# LitVP-02.net
KiCad netlist of a schematic drawn in Altium Designer
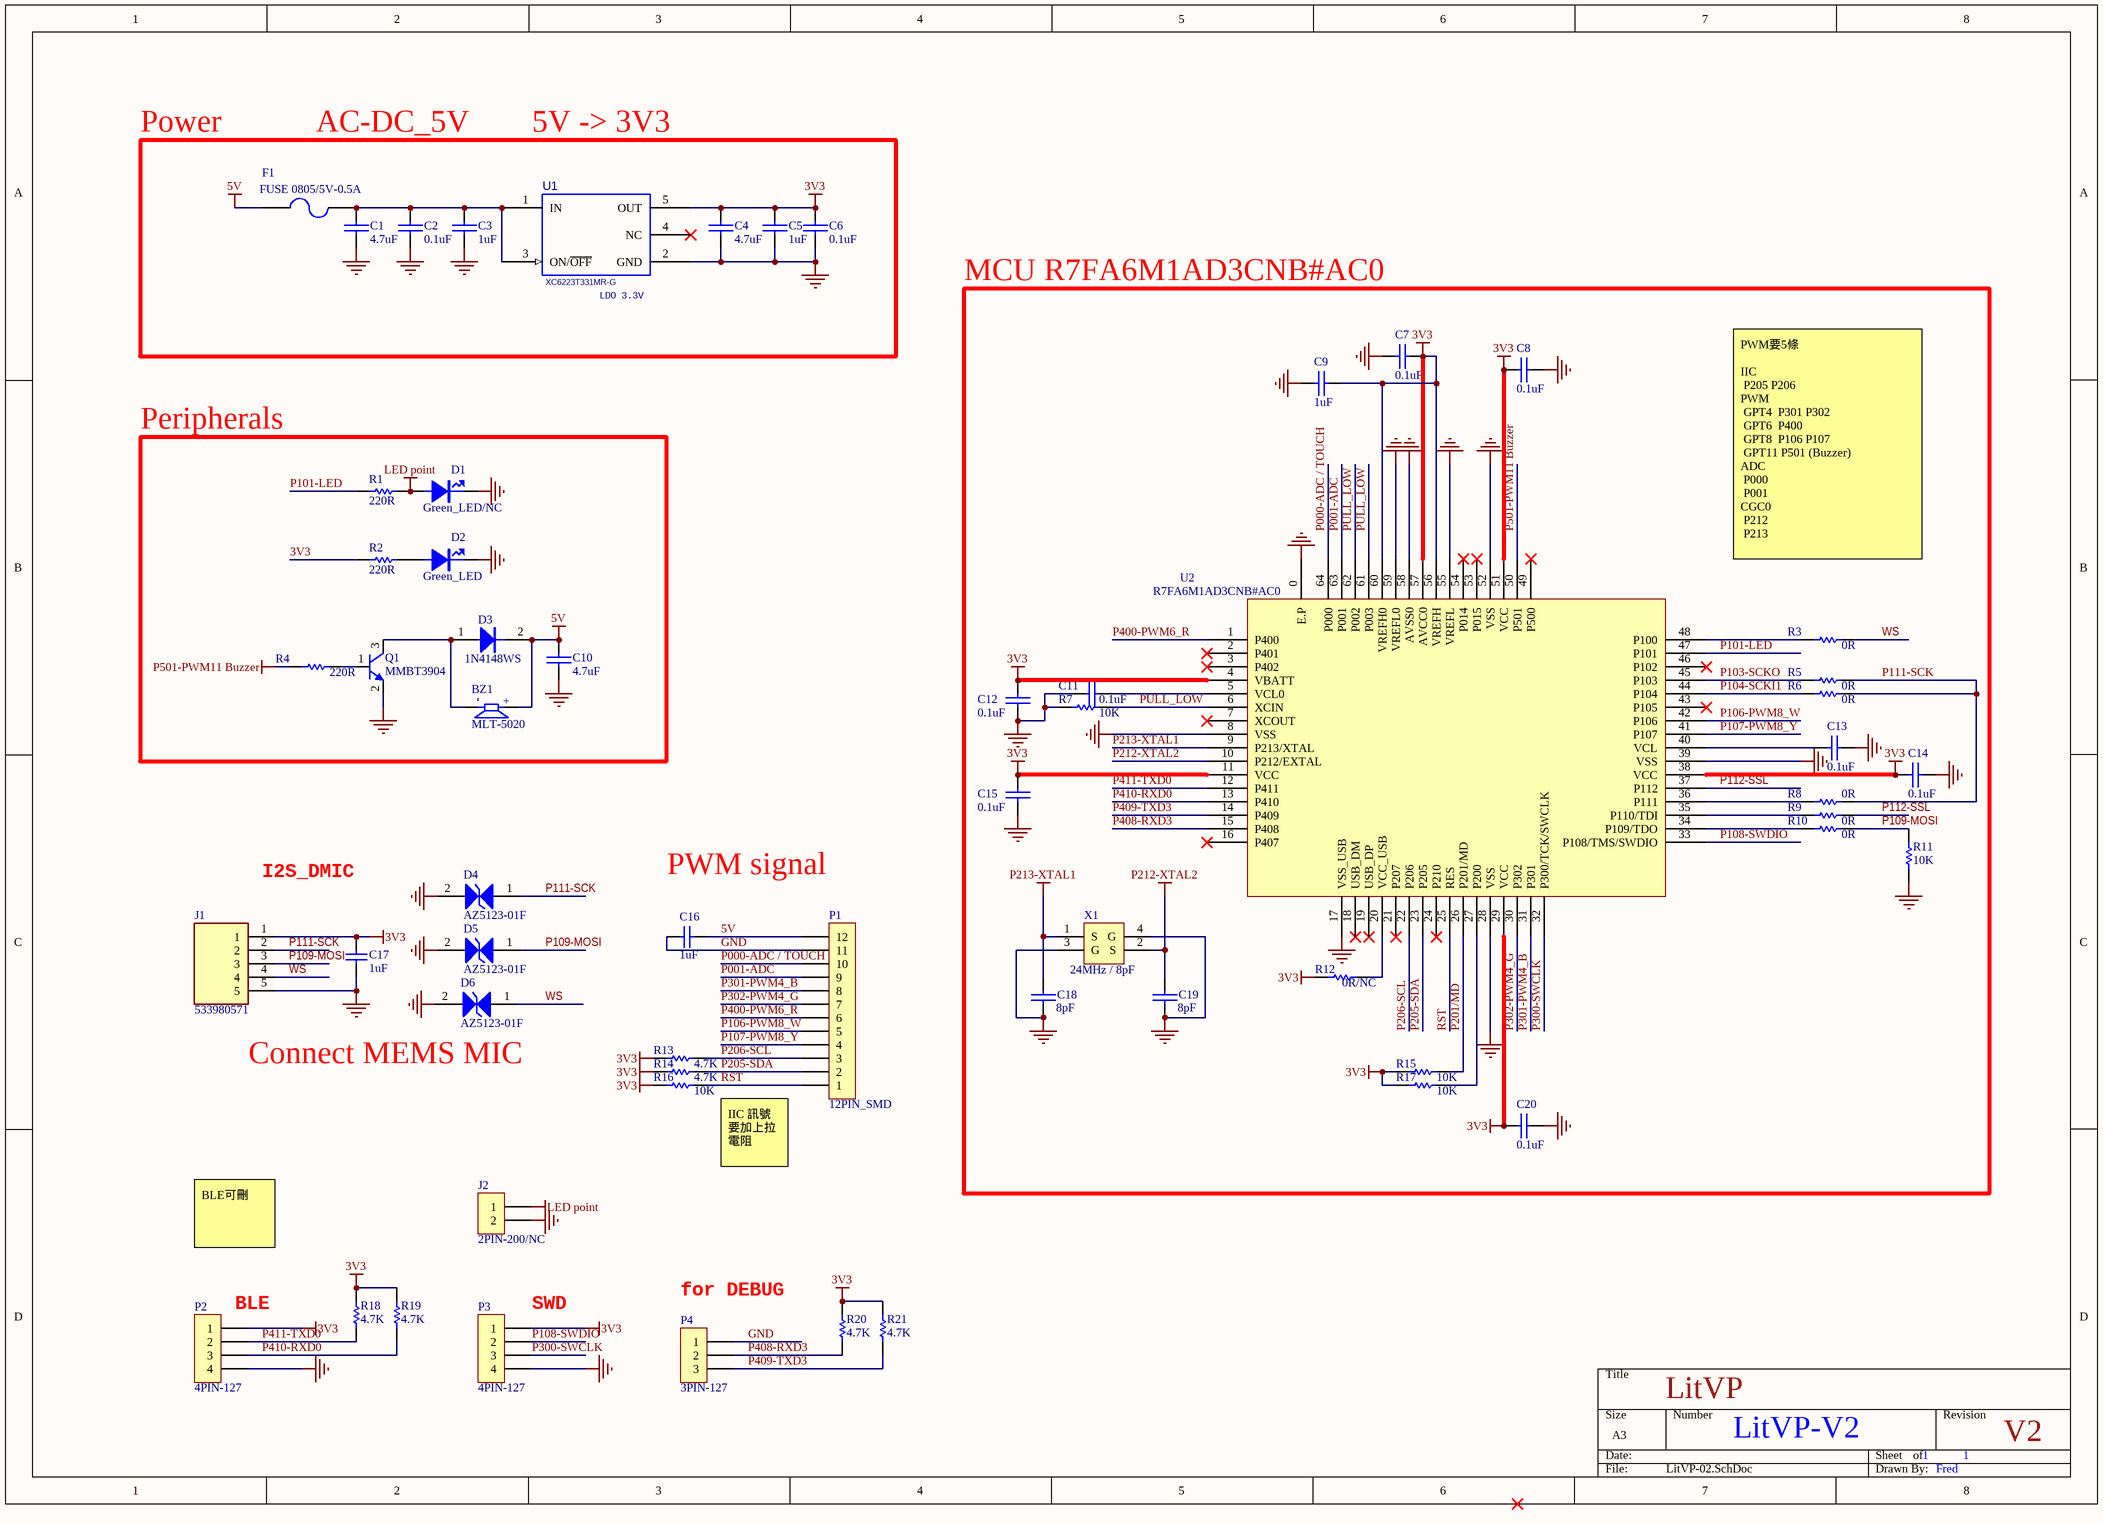
[diagram p0: LitVP-02.SchDoc]

(export (version "E")
  (design (tool "Eeschema 10.0.6"))
  (components
    (comp (ref "BZ1")
      (value "MLT-5020")
      (footprint "BUZZER-SMD-5*5mm")
      (description "Buzzer")
      (libsource (lib "*") (part "YZ5020CS-03L-4.0-12-R"))
    )
    (comp (ref "C1")
      (value "4.7uF")
      (footprint "0402C")
      (description "Capacitor")
      (libsource (lib "CAP") (part "CAP"))
    )
    (comp (ref "C2")
      (value "0.1uF")
      (footprint "0402C")
      (description "Capacitor")
      (libsource (lib "CAP") (part "CAP"))
    )
    (comp (ref "C3")
      (value "1uF")
      (footprint "0402C")
      (description "Capacitor")
      (libsource (lib "CAP") (part "CAP"))
    )
    (comp (ref "C4")
      (value "4.7uF")
      (footprint "0402C")
      (description "Capacitor")
      (libsource (lib "CAP") (part "CAP"))
    )
    (comp (ref "C5")
      (value "1uF")
      (footprint "0402C")
      (description "Capacitor")
      (libsource (lib "CAP") (part "CAP"))
    )
    (comp (ref "C6")
      (value "0.1uF")
      (footprint "0402C")
      (description "Capacitor")
      (libsource (lib "CAP") (part "CAP"))
    )
    (comp (ref "C7")
      (value "0.1uF")
      (footprint "0402C")
      (description "Capacitor")
      (libsource (lib "CAP") (part "CAP"))
    )
    (comp (ref "C8")
      (value "0.1uF")
      (footprint "0402C")
      (description "Capacitor")
      (libsource (lib "CAP") (part "CAP"))
    )
    (comp (ref "C9")
      (value "1uF")
      (footprint "0402C")
      (description "Capacitor")
      (libsource (lib "CAP") (part "CAP"))
    )
    (comp (ref "C10")
      (value "4.7uF")
      (footprint "0402C")
      (description "Capacitor")
      (libsource (lib "CAP") (part "CAP"))
    )
    (comp (ref "C11")
      (value "0.1uF")
      (footprint "0402C")
      (description "Capacitor")
      (libsource (lib "CAP") (part "CAP"))
    )
    (comp (ref "C12")
      (value "0.1uF")
      (footprint "0402C")
      (description "Capacitor")
      (libsource (lib "CAP") (part "CAP"))
    )
    (comp (ref "C13")
      (value "0.1uF")
      (footprint "0402C")
      (description "Capacitor")
      (libsource (lib "CAP") (part "CAP"))
    )
    (comp (ref "C14")
      (value "0.1uF")
      (footprint "0402C")
      (description "Capacitor")
      (libsource (lib "CAP") (part "CAP"))
    )
    (comp (ref "C15")
      (value "0.1uF")
      (footprint "0402C")
      (description "Capacitor")
      (libsource (lib "CAP") (part "CAP"))
    )
    (comp (ref "C16")
      (value "1uF")
      (footprint "0402C")
      (description "Capacitor")
      (libsource (lib "*") (part "Cap Semi"))
    )
    (comp (ref "C17")
      (value "1uF")
      (footprint "0402C")
      (description "Capacitor")
      (libsource (lib "*") (part "Cap Semi"))
    )
    (comp (ref "C18")
      (value "8pF")
      (footprint "0402C")
      (description "Capacitor")
      (libsource (lib "*") (part "CAP"))
    )
    (comp (ref "C19")
      (value "8pF")
      (footprint "0402C")
      (description "Capacitor")
      (libsource (lib "*") (part "CAP"))
    )
    (comp (ref "C20")
      (value "0.1uF")
      (footprint "0402C")
      (description "Capacitor")
      (libsource (lib "CAP") (part "CAP"))
    )
    (comp (ref "D1")
      (value "Green_LED/NC")
      (footprint "LED0603--0.4mm")
      (fields
        (field (name "MANUFACTURER'S PART NUMBER") "CL-170G-CD-T")
        (field (name "PART NUMBER") "41100017000")
        (field (name "MANUFACTURER") "Citizen")
      )
      (libsource (lib "*") (part "LED"))
    )
    (comp (ref "D2")
      (value "Green_LED")
      (footprint "LED0603--0.4mm")
      (fields
        (field (name "MANUFACTURER'S PART NUMBER") "CL-170G-CD-T")
        (field (name "PART NUMBER") "41100017000")
        (field (name "MANUFACTURER") "Citizen")
      )
      (libsource (lib "*") (part "LED"))
    )
    (comp (ref "D3") (value "1N4148WS") (footprint "SOD323-1N4148WS") (libsource (lib "*") (part "DIODE")))
    (comp (ref "D4")
      (value "AZ5123-01F")
      (footprint "DIODE-0402")
      (description "ESD")
      (libsource (lib "*") (part "PESD5V0L1BA"))
    )
    (comp (ref "D5")
      (value "AZ5123-01F")
      (footprint "DIODE-0402")
      (description "ESD")
      (libsource (lib "*") (part "PESD5V0L1BA"))
    )
    (comp (ref "D6")
      (value "AZ5123-01F")
      (footprint "DIODE-0402")
      (description "ESD")
      (libsource (lib "*") (part "PESD5V0L1BA"))
    )
    (comp (ref "F1")
      (value "FUSE 0805/5V-0.5A")
      (footprint "0805")
      (description "Fuse")
      (libsource (lib "*") (part "FUSE2"))
    )
    (comp (ref "J1")
      (value "533980571")
      (footprint "SamacSys:53398-0571")
      (description "Connector")
      (fields (field (name "MANUFACTURER_PART_NUMBER") "53048-0510"))
      (libsource (lib "*") (part "53048-0510"))
    )
    (comp (ref "J2")
      (value "2PIN-200/NC")
      (footprint "2PIN-127")
      (description "Connector")
      (libsource (lib "PIN") (part "2PIN-200"))
    )
    (comp (ref "P1")
      (value "12PIN_SMD")
      (footprint "12PIN_SAMTEC-MMT-136-02-X-SH")
      (libsource (lib "PIN") (part "12PIN_SMD"))
    )
    (comp (ref "P2")
      (value "4PIN-127")
      (footprint "4PIN-127")
      (description "1.27mm Header")
      (libsource (lib "*") (part "CON4"))
    )
    (comp (ref "P3")
      (value "4PIN-127")
      (footprint "4PIN-127")
      (description "1.27mm Header")
      (libsource (lib "*") (part "CON4"))
    )
    (comp (ref "P4") (value "3PIN-127") (footprint "3PIN-127") (libsource (lib "PIN") (part "3PIN-127")))
    (comp (ref "Q1")
      (value "MMBT3904")
      (footprint "SOT-23")
      (description "NPN General Purpose Amplifier")
      (fields (field (name "PUBLISHER") "*"))
      (libsource (lib "*") (part "NPN-3"))
    )
    (comp (ref "R1")
      (value "220R")
      (footprint "0402")
      (description "Resistor")
      (libsource (lib "*") (part "Res Semi"))
    )
    (comp (ref "R2")
      (value "220R")
      (footprint "0402")
      (description "Resistor")
      (libsource (lib "*") (part "Res Semi"))
    )
    (comp (ref "R3")
      (value "0R")
      (footprint "0402")
      (description "Resistor")
      (libsource (lib "*") (part "Res Semi"))
    )
    (comp (ref "R4")
      (value "220R")
      (footprint "0402")
      (description "Resistor")
      (libsource (lib "*") (part "Res Semi"))
    )
    (comp (ref "R5")
      (value "0R")
      (footprint "0402")
      (description "Resistor")
      (libsource (lib "*") (part "Res Semi"))
    )
    (comp (ref "R6")
      (value "0R")
      (footprint "0402")
      (description "Resistor")
      (libsource (lib "*") (part "Res Semi"))
    )
    (comp (ref "R7")
      (value "10K")
      (footprint "0402")
      (description "Resistor")
      (libsource (lib "*") (part "Res Semi"))
    )
    (comp (ref "R8")
      (value "0R")
      (footprint "0402")
      (description "Resistor")
      (libsource (lib "*") (part "Res Semi"))
    )
    (comp (ref "R9")
      (value "0R")
      (footprint "0402")
      (description "Resistor")
      (libsource (lib "*") (part "Res Semi"))
    )
    (comp (ref "R10")
      (value "0R")
      (footprint "0402")
      (description "Resistor")
      (libsource (lib "*") (part "Res Semi"))
    )
    (comp (ref "R11")
      (value "10K")
      (footprint "0402")
      (description "Resistor")
      (libsource (lib "*") (part "Res Semi"))
    )
    (comp (ref "R12")
      (value "0R/NC")
      (footprint "0402")
      (description "Resistor")
      (libsource (lib "*") (part "Res Semi"))
    )
    (comp (ref "R13")
      (value "4.7K")
      (footprint "0402")
      (description "Resistor")
      (libsource (lib "*") (part "Res Semi"))
    )
    (comp (ref "R14")
      (value "4.7K")
      (footprint "0402")
      (description "Resistor")
      (libsource (lib "*") (part "Res Semi"))
    )
    (comp (ref "R15")
      (value "10K")
      (footprint "0402")
      (description "Resistor")
      (libsource (lib "*") (part "Res Semi"))
    )
    (comp (ref "R16")
      (value "10K")
      (footprint "0402")
      (description "Resistor")
      (libsource (lib "*") (part "Res Semi"))
    )
    (comp (ref "R17")
      (value "10K")
      (footprint "0402")
      (description "Resistor")
      (libsource (lib "*") (part "Res Semi"))
    )
    (comp (ref "R18")
      (value "4.7K")
      (footprint "0402")
      (description "Resistor")
      (libsource (lib "*") (part "Res Semi"))
    )
    (comp (ref "R19")
      (value "4.7K")
      (footprint "0402")
      (description "Resistor")
      (libsource (lib "*") (part "Res Semi"))
    )
    (comp (ref "R20")
      (value "4.7K")
      (footprint "0402")
      (description "Resistor")
      (libsource (lib "*") (part "Res Semi"))
    )
    (comp (ref "R21")
      (value "4.7K")
      (footprint "0402")
      (description "Resistor")
      (libsource (lib "*") (part "Res Semi"))
    )
    (comp (ref "U1")
      (value "XC6223T331MR-G")
      (footprint "SOT-23-5-0.95MM")
      (libsource (lib "*") (part "XC6223T331MR-G"))
    )
    (comp (ref "U2")
      (value "R7FA6M1AD3CNB#AC0")
      (footprint "QFN64-0.4mm-8X8")
      (description "MCU")
      (libsource (lib "*") (part "R7FA6M1AD3CNB#AC0"))
    )
    (comp (ref "X1")
      (value "24MHz / 8pF")
      (footprint "XTAL-SMD-20X16")
      (libsource (lib "*") (part "XTAL-SMD-25*32"))
    )
  )
  (nets
    (net (code "1") (name "/P000-ADC {slash} TOUCH") (class "Default")
      (node (ref "P1") (pin "10") (pinfunction "10_10") (pintype "passive"))
      (node (ref "U2") (pin "64") (pinfunction "P000_64") (pintype "passive"))
    )
    (net (code "2") (name "/P001-ADC") (class "Default")
      (node (ref "P1") (pin "9") (pinfunction "9_9") (pintype "passive"))
      (node (ref "U2") (pin "63") (pinfunction "P001_63") (pintype "passive"))
    )
    (net (code "3") (name "/P101-LED") (class "Default")
      (node (ref "R1") (pin "1") (pinfunction "1_1") (pintype "passive"))
      (node (ref "U2") (pin "47") (pinfunction "P101_47") (pintype "passive"))
    )
    (net (code "4") (name "/P103-SCKO") (class "Default")
      (node (ref "R5") (pin "2") (pinfunction "2_2") (pintype "passive"))
      (node (ref "U2") (pin "45") (pinfunction "P103_45") (pintype "passive"))
    )
    (net (code "5") (name "/P104-SCKI1") (class "Default")
      (node (ref "R6") (pin "2") (pinfunction "2_2") (pintype "passive"))
      (node (ref "U2") (pin "44") (pinfunction "P104_44") (pintype "passive"))
    )
    (net (code "6") (name "/P106-PWM8_W") (class "Default")
      (node (ref "P1") (pin "5") (pinfunction "5_5") (pintype "passive"))
      (node (ref "U2") (pin "42") (pinfunction "P106_42") (pintype "passive"))
    )
    (net (code "7") (name "/P107-PWM8_Y") (class "Default")
      (node (ref "P1") (pin "4") (pinfunction "4_4") (pintype "passive"))
      (node (ref "U2") (pin "41") (pinfunction "P107_41") (pintype "passive"))
    )
    (net (code "8") (name "/P108-SWDIO") (class "Default")
      (node (ref "P3") (pin "2") (pinfunction "2_2") (pintype "passive"))
      (node (ref "U2") (pin "33") (pinfunction "P108/TMS/SWDIO_33") (pintype "passive"))
    )
    (net (code "9") (name "/P109-MOSI") (class "Default")
      (node (ref "D5") (pin "1") (pinfunction "1_1") (pintype "passive"))
      (node (ref "J1") (pin "3") (pinfunction "3_3") (pintype "passive"))
      (node (ref "R10") (pin "1") (pinfunction "1_1") (pintype "passive"))
      (node (ref "R11") (pin "2") (pinfunction "2_2") (pintype "passive"))
    )
    (net (code "10") (name "/P111-SCK") (class "Default")
      (node (ref "D4") (pin "1") (pinfunction "1_1") (pintype "passive"))
      (node (ref "J1") (pin "2") (pinfunction "2_2") (pintype "passive"))
      (node (ref "R5") (pin "1") (pinfunction "1_1") (pintype "passive"))
      (node (ref "R6") (pin "1") (pinfunction "1_1") (pintype "passive"))
      (node (ref "R8") (pin "1") (pinfunction "1_1") (pintype "passive"))
    )
    (net (code "11") (name "/P112-SSL") (class "Default")
      (node (ref "R9") (pin "1") (pinfunction "1_1") (pintype "passive"))
      (node (ref "U2") (pin "37") (pinfunction "P112_37") (pintype "passive"))
    )
    (net (code "12") (name "/P201{slash}MD") (class "Default")
      (node (ref "R15") (pin "1") (pinfunction "1_1") (pintype "passive"))
      (node (ref "U2") (pin "26") (pinfunction "P201/MD_26") (pintype "passive"))
    )
    (net (code "13") (name "/P205-SDA") (class "Default")
      (node (ref "P1") (pin "2") (pinfunction "2_2") (pintype "passive"))
      (node (ref "R14") (pin "1") (pinfunction "1_1") (pintype "passive"))
      (node (ref "U2") (pin "23") (pinfunction "P205_23") (pintype "passive"))
    )
    (net (code "14") (name "/P206-SCL") (class "Default")
      (node (ref "P1") (pin "3") (pinfunction "3_3") (pintype "passive"))
      (node (ref "R13") (pin "1") (pinfunction "1_1") (pintype "passive"))
      (node (ref "U2") (pin "22") (pinfunction "P206_22") (pintype "passive"))
    )
    (net (code "15") (name "/P300-SWCLK") (class "Default")
      (node (ref "P3") (pin "3") (pinfunction "3_3") (pintype "passive"))
      (node (ref "U2") (pin "32") (pinfunction "P300/TCK/SWCLK_32") (pintype "passive"))
    )
    (net (code "16") (name "/P301-PWM4_B") (class "Default")
      (node (ref "P1") (pin "8") (pinfunction "8_8") (pintype "passive"))
      (node (ref "U2") (pin "31") (pinfunction "P301_31") (pintype "passive"))
    )
    (net (code "17") (name "/P302-PWM4_G") (class "Default")
      (node (ref "P1") (pin "7") (pinfunction "7_7") (pintype "passive"))
      (node (ref "U2") (pin "30") (pinfunction "P302_30") (pintype "passive"))
    )
    (net (code "18") (name "/P400-PWM6_R") (class "Default")
      (node (ref "P1") (pin "6") (pinfunction "6_6") (pintype "passive"))
      (node (ref "U2") (pin "1") (pinfunction "P400_1") (pintype "passive"))
    )
    (net (code "19") (name "/P408-RXD3") (class "Default")
      (node (ref "P4") (pin "2") (pinfunction "2_2") (pintype "passive"))
      (node (ref "R20") (pin "2") (pinfunction "2_2") (pintype "passive"))
      (node (ref "U2") (pin "15") (pinfunction "P408_15") (pintype "passive"))
    )
    (net (code "20") (name "/P409-TXD3") (class "Default")
      (node (ref "P4") (pin "3") (pinfunction "3_3") (pintype "passive"))
      (node (ref "R21") (pin "2") (pinfunction "2_2") (pintype "passive"))
      (node (ref "U2") (pin "14") (pinfunction "P409_14") (pintype "passive"))
    )
    (net (code "21") (name "/P410-RXD0") (class "Default")
      (node (ref "P2") (pin "3") (pinfunction "3_3") (pintype "passive"))
      (node (ref "R19") (pin "2") (pinfunction "2_2") (pintype "passive"))
      (node (ref "U2") (pin "13") (pinfunction "P410_13") (pintype "passive"))
    )
    (net (code "22") (name "/P411-TXD0") (class "Default")
      (node (ref "P2") (pin "2") (pinfunction "2_2") (pintype "passive"))
      (node (ref "R18") (pin "2") (pinfunction "2_2") (pintype "passive"))
      (node (ref "U2") (pin "12") (pinfunction "P411_12") (pintype "passive"))
    )
    (net (code "23") (name "/PULL_LOW") (class "Default")
      (node (ref "R7") (pin "1") (pinfunction "1_1") (pintype "passive"))
      (node (ref "U2") (pin "6") (pinfunction "XCIN_6") (pintype "passive"))
      (node (ref "U2") (pin "61") (pinfunction "P003_61") (pintype "passive"))
      (node (ref "U2") (pin "62") (pinfunction "P002_62") (pintype "passive"))
    )
    (net (code "24") (name "/RST") (class "Default")
      (node (ref "P1") (pin "1") (pinfunction "1_1") (pintype "passive"))
      (node (ref "R16") (pin "1") (pinfunction "1_1") (pintype "passive"))
      (node (ref "U2") (pin "25") (pinfunction "RES_25") (pintype "passive"))
    )
    (net (code "25") (name "/WS") (class "Default")
      (node (ref "D6") (pin "1") (pinfunction "1_1") (pintype "passive"))
      (node (ref "J1") (pin "4") (pinfunction "4_4") (pintype "passive"))
      (node (ref "R3") (pin "1") (pinfunction "1_1") (pintype "passive"))
    )
    (net (code "26") (name "3V3") (class "Default")
      (node (ref "C12") (pin "2") (pinfunction "2_2") (pintype "passive"))
      (node (ref "C14") (pin "2") (pinfunction "2_2") (pintype "passive"))
      (node (ref "C15") (pin "2") (pinfunction "2_2") (pintype "passive"))
      (node (ref "C17") (pin "2") (pinfunction "2_2") (pintype "passive"))
      (node (ref "C20") (pin "2") (pinfunction "2_2") (pintype "passive"))
      (node (ref "C4") (pin "1") (pinfunction "1_1") (pintype "passive"))
      (node (ref "C5") (pin "1") (pinfunction "1_1") (pintype "passive"))
      (node (ref "C6") (pin "1") (pinfunction "1_1") (pintype "passive"))
      (node (ref "C7") (pin "2") (pinfunction "2_2") (pintype "passive"))
      (node (ref "C8") (pin "1") (pinfunction "1_1") (pintype "passive"))
      (node (ref "C9") (pin "2") (pinfunction "2_2") (pintype "passive"))
      (node (ref "J1") (pin "1") (pinfunction "1_1") (pintype "passive"))
      (node (ref "P2") (pin "1") (pinfunction "1_1") (pintype "passive"))
      (node (ref "P3") (pin "1") (pinfunction "1_1") (pintype "passive"))
      (node (ref "R12") (pin "2") (pinfunction "2_2") (pintype "passive"))
      (node (ref "R13") (pin "2") (pinfunction "2_2") (pintype "passive"))
      (node (ref "R14") (pin "2") (pinfunction "2_2") (pintype "passive"))
      (node (ref "R15") (pin "2") (pinfunction "2_2") (pintype "passive"))
      (node (ref "R16") (pin "2") (pinfunction "2_2") (pintype "passive"))
      (node (ref "R17") (pin "2") (pinfunction "2_2") (pintype "passive"))
      (node (ref "R18") (pin "1") (pinfunction "1_1") (pintype "passive"))
      (node (ref "R19") (pin "1") (pinfunction "1_1") (pintype "passive"))
      (node (ref "R2") (pin "1") (pinfunction "1_1") (pintype "passive"))
      (node (ref "R20") (pin "1") (pinfunction "1_1") (pintype "passive"))
      (node (ref "R21") (pin "1") (pinfunction "1_1") (pintype "passive"))
      (node (ref "U1") (pin "5") (pinfunction "OUT_5") (pintype "passive"))
      (node (ref "U2") (pin "11") (pinfunction "VCC_11") (pintype "passive"))
      (node (ref "U2") (pin "29") (pinfunction "VCC_29") (pintype "passive"))
      (node (ref "U2") (pin "38") (pinfunction "VCC_38") (pintype "passive"))
      (node (ref "U2") (pin "4") (pinfunction "VBATT_4") (pintype "passive"))
      (node (ref "U2") (pin "51") (pinfunction "VCC_51") (pintype "passive"))
      (node (ref "U2") (pin "56") (pinfunction "VREFH_56") (pintype "passive"))
      (node (ref "U2") (pin "57") (pinfunction "AVCC0_57") (pintype "passive"))
      (node (ref "U2") (pin "60") (pinfunction "VREFH0_60") (pintype "passive"))
    )
    (net (code "27") (name "5V") (class "Default")
      (node (ref "BZ1") (pin "1") (pinfunction "1_1") (pintype "passive"))
      (node (ref "C10") (pin "1") (pinfunction "1_1") (pintype "passive"))
      (node (ref "C16") (pin "1") (pinfunction "1_1") (pintype "passive"))
      (node (ref "D3") (pin "2") (pinfunction "2_2") (pintype "passive"))
      (node (ref "F1") (pin "1") (pinfunction "1_1") (pintype "passive"))
      (node (ref "P1") (pin "12") (pinfunction "12_12") (pintype "passive"))
    )
    (net (code "28") (name "GND") (class "Default")
      (node (ref "C1") (pin "2") (pinfunction "2_2") (pintype "passive"))
      (node (ref "C10") (pin "2") (pinfunction "2_2") (pintype "passive"))
      (node (ref "C11") (pin "2") (pinfunction "2_2") (pintype "passive"))
      (node (ref "C12") (pin "1") (pinfunction "1_1") (pintype "passive"))
      (node (ref "C13") (pin "1") (pinfunction "1_1") (pintype "passive"))
      (node (ref "C14") (pin "1") (pinfunction "1_1") (pintype "passive"))
      (node (ref "C15") (pin "1") (pinfunction "1_1") (pintype "passive"))
      (node (ref "C16") (pin "2") (pinfunction "2_2") (pintype "passive"))
      (node (ref "C17") (pin "1") (pinfunction "1_1") (pintype "passive"))
      (node (ref "C18") (pin "2") (pinfunction "2_2") (pintype "passive"))
      (node (ref "C19") (pin "2") (pinfunction "2_2") (pintype "passive"))
      (node (ref "C2") (pin "2") (pinfunction "2_2") (pintype "passive"))
      (node (ref "C20") (pin "1") (pinfunction "1_1") (pintype "passive"))
      (node (ref "C3") (pin "2") (pinfunction "2_2") (pintype "passive"))
      (node (ref "C4") (pin "2") (pinfunction "2_2") (pintype "passive"))
      (node (ref "C5") (pin "2") (pinfunction "2_2") (pintype "passive"))
      (node (ref "C6") (pin "2") (pinfunction "2_2") (pintype "passive"))
      (node (ref "C7") (pin "1") (pinfunction "1_1") (pintype "passive"))
      (node (ref "C8") (pin "2") (pinfunction "2_2") (pintype "passive"))
      (node (ref "C9") (pin "1") (pinfunction "1_1") (pintype "passive"))
      (node (ref "D1") (pin "2") (pinfunction "2_2") (pintype "passive"))
      (node (ref "D2") (pin "2") (pinfunction "2_2") (pintype "passive"))
      (node (ref "D4") (pin "2") (pinfunction "2_2") (pintype "passive"))
      (node (ref "D5") (pin "2") (pinfunction "2_2") (pintype "passive"))
      (node (ref "D6") (pin "2") (pinfunction "2_2") (pintype "passive"))
      (node (ref "J1") (pin "5") (pinfunction "5_5") (pintype "passive"))
      (node (ref "J2") (pin "2") (pinfunction "2_2") (pintype "passive"))
      (node (ref "P1") (pin "11") (pinfunction "11_11") (pintype "passive"))
      (node (ref "P2") (pin "4") (pinfunction "4_4") (pintype "passive"))
      (node (ref "P3") (pin "4") (pinfunction "4_4") (pintype "passive"))
      (node (ref "P4") (pin "1") (pinfunction "1_1") (pintype "passive"))
      (node (ref "Q1") (pin "2") (pinfunction "E_2") (pintype "passive"))
      (node (ref "R11") (pin "1") (pinfunction "1_1") (pintype "passive"))
      (node (ref "R7") (pin "2") (pinfunction "2_2") (pintype "passive"))
      (node (ref "U1") (pin "2") (pinfunction "GND_2") (pintype "passive"))
      (node (ref "U2") (pin "0") (pinfunction "E.P_0") (pintype "passive"))
      (node (ref "U2") (pin "17") (pinfunction "VSS_USB_17") (pintype "passive"))
      (node (ref "U2") (pin "28") (pinfunction "VSS_28") (pintype "passive"))
      (node (ref "U2") (pin "39") (pinfunction "VSS_39") (pintype "passive"))
      (node (ref "U2") (pin "52") (pinfunction "VSS_52") (pintype "passive"))
      (node (ref "U2") (pin "55") (pinfunction "VREFL_55") (pintype "passive"))
      (node (ref "U2") (pin "58") (pinfunction "AVSS0_58") (pintype "passive"))
      (node (ref "U2") (pin "59") (pinfunction "VREFL0_59") (pintype "passive"))
      (node (ref "U2") (pin "8") (pinfunction "VSS_8") (pintype "passive"))
      (node (ref "X1") (pin "3") (pinfunction "G_3") (pintype "passive"))
      (node (ref "X1") (pin "4") (pinfunction "G_4") (pintype "passive"))
    )
    (net (code "29") (name "LED point") (class "Default")
      (node (ref "D1") (pin "1") (pinfunction "1_1") (pintype "passive"))
      (node (ref "J2") (pin "1") (pinfunction "1_1") (pintype "passive"))
      (node (ref "R1") (pin "2") (pinfunction "2_2") (pintype "passive"))
    )
    (net (code "30") (name "Net-(D2-Pad1)") (class "Default")
      (node (ref "D2") (pin "1") (pinfunction "1_1") (pintype "passive"))
      (node (ref "R2") (pin "2") (pinfunction "2_2") (pintype "passive"))
    )
    (net (code "31") (name "Net-(Q1-B)") (class "Default")
      (node (ref "Q1") (pin "1") (pinfunction "B_1") (pintype "passive"))
      (node (ref "R4") (pin "1") (pinfunction "1_1") (pintype "passive"))
    )
    (net (code "32") (name "Net-(Q1-C)") (class "Default")
      (node (ref "BZ1") (pin "2") (pinfunction "2_2") (pintype "passive"))
      (node (ref "D3") (pin "1") (pinfunction "1_1") (pintype "passive"))
      (node (ref "Q1") (pin "3") (pinfunction "C_3") (pintype "passive"))
    )
    (net (code "33") (name "Net-(U1-IN)") (class "Default")
      (node (ref "C1") (pin "1") (pinfunction "1_1") (pintype "passive"))
      (node (ref "C2") (pin "1") (pinfunction "1_1") (pintype "passive"))
      (node (ref "C3") (pin "1") (pinfunction "1_1") (pintype "passive"))
      (node (ref "F1") (pin "2") (pinfunction "2_2") (pintype "passive"))
      (node (ref "U1") (pin "1") (pinfunction "IN_1") (pintype "passive"))
      (node (ref "U1") (pin "3") (pinfunction "ON/~{OFF}_3") (pintype "input"))
    )
    (net (code "34") (name "Net-(U2-P100)") (class "Default")
      (node (ref "R3") (pin "2") (pinfunction "2_2") (pintype "passive"))
      (node (ref "U2") (pin "48") (pinfunction "P100_48") (pintype "passive"))
    )
    (net (code "35") (name "Net-(U2-P109{slash}TDO)") (class "Default")
      (node (ref "R10") (pin "2") (pinfunction "2_2") (pintype "passive"))
      (node (ref "U2") (pin "34") (pinfunction "P109/TDO_34") (pintype "passive"))
    )
    (net (code "36") (name "Net-(U2-P110{slash}TDI)") (class "Default")
      (node (ref "R9") (pin "2") (pinfunction "2_2") (pintype "passive"))
      (node (ref "U2") (pin "35") (pinfunction "P110/TDI_35") (pintype "passive"))
    )
    (net (code "37") (name "Net-(U2-P111)") (class "Default")
      (node (ref "R8") (pin "2") (pinfunction "2_2") (pintype "passive"))
      (node (ref "U2") (pin "36") (pinfunction "P111_36") (pintype "passive"))
    )
    (net (code "38") (name "Net-(U2-P200)") (class "Default")
      (node (ref "R17") (pin "1") (pinfunction "1_1") (pintype "passive"))
      (node (ref "U2") (pin "27") (pinfunction "P200_27") (pintype "passive"))
    )
    (net (code "39") (name "Net-(U2-VCC_USB)") (class "Default")
      (node (ref "R12") (pin "1") (pinfunction "1_1") (pintype "passive"))
      (node (ref "U2") (pin "20") (pinfunction "VCC_USB_20") (pintype "passive"))
    )
    (net (code "40") (name "Net-(U2-VCL)") (class "Default")
      (node (ref "C13") (pin "2") (pinfunction "2_2") (pintype "passive"))
      (node (ref "U2") (pin "40") (pinfunction "VCL_40") (pintype "passive"))
    )
    (net (code "41") (name "Net-(U2-VCL0)") (class "Default")
      (node (ref "C11") (pin "1") (pinfunction "1_1") (pintype "passive"))
      (node (ref "U2") (pin "5") (pinfunction "VCL0_5") (pintype "passive"))
    )
    (net (code "42") (name "P212-XTAL2") (class "Default")
      (node (ref "C19") (pin "1") (pinfunction "1_1") (pintype "passive"))
      (node (ref "U2") (pin "10") (pinfunction "P212/EXTAL_10") (pintype "passive"))
      (node (ref "X1") (pin "2") (pinfunction "S_2") (pintype "passive"))
    )
    (net (code "43") (name "P213-XTAL1") (class "Default")
      (node (ref "C18") (pin "1") (pinfunction "1_1") (pintype "passive"))
      (node (ref "U2") (pin "9") (pinfunction "P213/XTAL_9") (pintype "passive"))
      (node (ref "X1") (pin "1") (pinfunction "S_1") (pintype "passive"))
    )
    (net (code "44") (name "P501-PWM11 Buzzer") (class "Default")
      (node (ref "R4") (pin "2") (pinfunction "2_2") (pintype "passive"))
      (node (ref "U2") (pin "50") (pinfunction "P501_50") (pintype "passive"))
    )
    (net (code "45") (name "unconnected-(U1-NC-Pad4)") (class "Default")
      (node (ref "U1") (pin "4") (pinfunction "NC_4") (pintype "passive+no_connect"))
    )
    (net (code "46") (name "unconnected-(U2-P014-Pad54)") (class "Default")
      (node (ref "U2") (pin "54") (pinfunction "P014_54") (pintype "passive+no_connect"))
    )
    (net (code "47") (name "unconnected-(U2-P015-Pad53)") (class "Default")
      (node (ref "U2") (pin "53") (pinfunction "P015_53") (pintype "passive+no_connect"))
    )
    (net (code "48") (name "unconnected-(U2-P102-Pad46)") (class "Default")
      (node (ref "U2") (pin "46") (pinfunction "P102_46") (pintype "passive+no_connect"))
    )
    (net (code "49") (name "unconnected-(U2-P105-Pad43)") (class "Default")
      (node (ref "U2") (pin "43") (pinfunction "P105_43") (pintype "passive+no_connect"))
    )
    (net (code "50") (name "unconnected-(U2-P207-Pad21)") (class "Default")
      (node (ref "U2") (pin "21") (pinfunction "P207_21") (pintype "passive+no_connect"))
    )
    (net (code "51") (name "unconnected-(U2-P210-Pad24)") (class "Default")
      (node (ref "U2") (pin "24") (pinfunction "P210_24") (pintype "passive+no_connect"))
    )
    (net (code "52") (name "unconnected-(U2-P401-Pad2)") (class "Default")
      (node (ref "U2") (pin "2") (pinfunction "P401_2") (pintype "passive+no_connect"))
    )
    (net (code "53") (name "unconnected-(U2-P402-Pad3)") (class "Default")
      (node (ref "U2") (pin "3") (pinfunction "P402_3") (pintype "passive+no_connect"))
    )
    (net (code "54") (name "unconnected-(U2-P407-Pad16)") (class "Default")
      (node (ref "U2") (pin "16") (pinfunction "P407_16") (pintype "passive+no_connect"))
    )
    (net (code "55") (name "unconnected-(U2-P500-Pad49)") (class "Default")
      (node (ref "U2") (pin "49") (pinfunction "P500_49") (pintype "passive+no_connect"))
    )
    (net (code "56") (name "unconnected-(U2-USB_DM-Pad18)") (class "Default")
      (node (ref "U2") (pin "18") (pinfunction "USB_DM_18") (pintype "passive+no_connect"))
    )
    (net (code "57") (name "unconnected-(U2-USB_DP-Pad19)") (class "Default")
      (node (ref "U2") (pin "19") (pinfunction "USB_DP_19") (pintype "passive+no_connect"))
    )
    (net (code "58") (name "unconnected-(U2-XCOUT-Pad7)") (class "Default")
      (node (ref "U2") (pin "7") (pinfunction "XCOUT_7") (pintype "passive+no_connect"))
    )
  )
)
